# RamanPowerBoard.net
KiCad netlist of a schematic drawn in Altium Designer
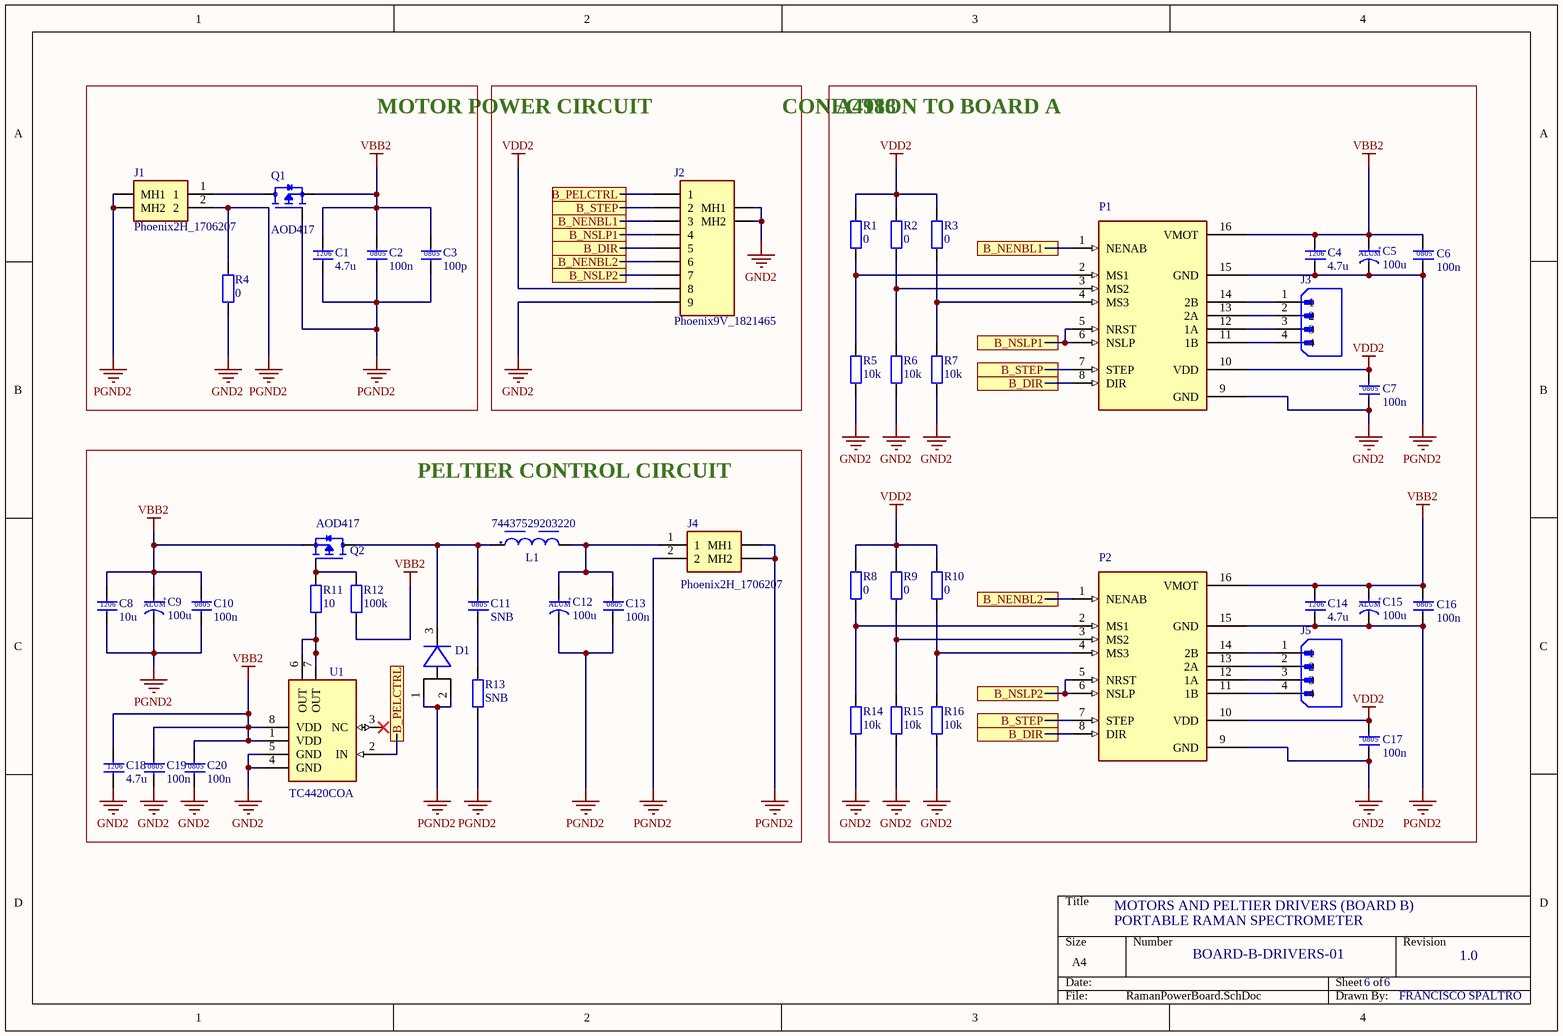
[diagram p0: RamanPowerBoard.SchDoc]

(export (version "E")
  (design (tool "Eeschema 10.0.6"))
  (components
    (comp (ref "C1")
      (value "4.7u")
      (footprint "CAP_1206")
      (description "Taiyo Yuden UMK316AB7475KL-T")
      (libsource (lib "Components") (part "CAP_1206"))
    )
    (comp (ref "C2")
      (value "100n")
      (footprint "RES_0805")
      (description "0805 Capacitor without polarity")
      (libsource (lib "Components") (part "CAP_0805"))
    )
    (comp (ref "C3")
      (value "100p")
      (footprint "RES_0805")
      (description "0805 Capacitor without polarity")
      (libsource (lib "Components") (part "CAP_0805"))
    )
    (comp (ref "C4")
      (value "4.7u")
      (footprint "CAP_1206")
      (description "Taiyo Yuden UMK316AB7475KL-T")
      (libsource (lib "Components") (part "CAP_1206"))
    )
    (comp (ref "C5")
      (value "100u")
      (footprint "CAP_EEFK_D8_PAN-M")
      (description "Panasonic EEE-FK1V101XP")
      (libsource (lib "Components") (part "CAP_RAD_POL"))
    )
    (comp (ref "C6")
      (value "100n")
      (footprint "RES_0805")
      (description "0805 Capacitor without polarity")
      (libsource (lib "Components") (part "CAP_0805"))
    )
    (comp (ref "C7")
      (value "100n")
      (footprint "RES_0805")
      (description "0805 Capacitor without polarity")
      (libsource (lib "Components") (part "CAP_0805"))
    )
    (comp (ref "C8")
      (value "10u")
      (footprint "CAP_1206")
      (description "Samsung CL31A106KAHNNNE")
      (libsource (lib "Components") (part "CAP_1206"))
    )
    (comp (ref "C9")
      (value "100u")
      (footprint "CAP_EEFK_D8_PAN-M")
      (description "Panasonic EEE-FK1V101XP")
      (libsource (lib "Components") (part "CAP_RAD_POL"))
    )
    (comp (ref "C10")
      (value "100n")
      (footprint "RES_0805")
      (description "0805 Capacitor without polarity")
      (libsource (lib "Components") (part "CAP_0805"))
    )
    (comp (ref "C11")
      (value "SNB")
      (footprint "RES_0805")
      (description "0805 Capacitor without polarity")
      (libsource (lib "Components") (part "CAP_0805"))
    )
    (comp (ref "C12")
      (value "100u")
      (footprint "CAP_EEFK_D8_PAN-M")
      (description "Panasonic EEE-FK1V101XP")
      (libsource (lib "Components") (part "CAP_RAD_POL"))
    )
    (comp (ref "C13")
      (value "100n")
      (footprint "RES_0805")
      (description "0805 Capacitor without polarity")
      (libsource (lib "Components") (part "CAP_0805"))
    )
    (comp (ref "C14")
      (value "4.7u")
      (footprint "CAP_1206")
      (description "Taiyo Yuden UMK316AB7475KL-T")
      (libsource (lib "Components") (part "CAP_1206"))
    )
    (comp (ref "C15")
      (value "100u")
      (footprint "CAP_EEFK_D8_PAN-M")
      (description "Panasonic EEE-FK1V101XP")
      (libsource (lib "Components") (part "CAP_RAD_POL"))
    )
    (comp (ref "C16")
      (value "100n")
      (footprint "RES_0805")
      (description "0805 Capacitor without polarity")
      (libsource (lib "Components") (part "CAP_0805"))
    )
    (comp (ref "C17")
      (value "100n")
      (footprint "RES_0805")
      (description "0805 Capacitor without polarity")
      (libsource (lib "Components") (part "CAP_0805"))
    )
    (comp (ref "C18")
      (value "4.7u")
      (footprint "CAP_1206")
      (description "Taiyo Yuden UMK316AB7475KL-T")
      (libsource (lib "Components") (part "CAP_1206"))
    )
    (comp (ref "C19")
      (value "100n")
      (footprint "RES_0805")
      (description "0805 Capacitor without polarity")
      (libsource (lib "Components") (part "CAP_0805"))
    )
    (comp (ref "C20")
      (value "100n")
      (footprint "RES_0805")
      (description "0805 Capacitor without polarity")
      (libsource (lib "Components") (part "CAP_0805"))
    )
    (comp (ref "D1")
      (value "DIODE_FSV15150V")
      (footprint "FSV15150V_TO-277")
      (libsource (lib "Components") (part "DIODE_FSV15150V"))
    )
    (comp (ref "J1")
      (value "Phoenix2H_1706207")
      (footprint "PHOENIX_1706207")
      (fields (field (name "MP") "1706207"))
      (libsource (lib "Components") (part "Phoenix2H_1706207"))
    )
    (comp (ref "J2")
      (value "Phoenix9V_1821465")
      (footprint "PHOENIX_1821465")
      (fields (field (name "MF") "{'manufacturer': u'Phoenix Contact'}") (field (name "MP") "1821465"))
      (libsource (lib "Components") (part "Phoenix9V_1821465"))
    )
    (comp (ref "J3")
      (value "Molex_4P")
      (footprint "MOLEX_436500402")
      (description "Connector Header Through Hole, Right Angle 4 position 0.118 (3.00mm) (Molex 436500402)")
      (fields (field (name "MF") "Molex") (field (name "MP") "436500402"))
      (libsource (lib "Components") (part "Molex_4P"))
    )
    (comp (ref "J4")
      (value "Phoenix2H_1706207")
      (footprint "PHOENIX_1706207")
      (fields (field (name "MP") "1706207"))
      (libsource (lib "") (part "Phoenix2H_1706207_1"))
    )
    (comp (ref "J5")
      (value "Molex_4P")
      (footprint "MOLEX_436500402")
      (description "Connector Header Through Hole, Right Angle 4 position 0.118 (3.00mm) (Molex 436500402)")
      (fields (field (name "MF") "Molex") (field (name "MP") "436500402"))
      (libsource (lib "Components") (part "Molex_4P"))
    )
    (comp (ref "L1")
      (value "74437529203220")
      (footprint "WE-HCF_2920_ROUND")
      (fields (field (name "MF") "{'manufacturer': u'~{W}xfcrth Elektronik'}"))
      (libsource (lib "Components") (part "22uH_74437529203220"))
    )
    (comp (ref "P1")
      (value "2x8_PINES")
      (footprint "PINES8x2-sep")
      (libsource (lib "Components") (part "2x8_PINES"))
    )
    (comp (ref "P2")
      (value "2x8_PINES")
      (footprint "PINES8x2-sep")
      (libsource (lib "Components") (part "2x8_PINES"))
    )
    (comp (ref "Q1")
      (value "AOD417")
      (footprint "Components:DPAK228P994X240_3N")
      (description "P-Channel 30V 25A _Ta_ 2.5W _Ta_, 50W _Tc_ Surface Mount TO-252, _D-Pak_")
      (fields (field (name "MF") "Alpha &"))
      (libsource (lib "Components") (part "AOD417"))
    )
    (comp (ref "Q2")
      (value "AOD417")
      (footprint "Components:DPAK228P994X240_3N")
      (description "P-Channel 30V 25A _Ta_ 2.5W _Ta_, 50W _Tc_ Surface Mount TO-252, _D-Pak_")
      (fields (field (name "MF") "Alpha &"))
      (libsource (lib "Components") (part "AOD417"))
    )
    (comp (ref "R1")
      (value "0")
      (footprint "RES_0805")
      (description "Generic Capacitor")
      (libsource (lib "Components") (part "RES_0805"))
    )
    (comp (ref "R2")
      (value "0")
      (footprint "RES_0805")
      (description "Generic Capacitor")
      (libsource (lib "Components") (part "RES_0805"))
    )
    (comp (ref "R3")
      (value "0")
      (footprint "RES_0805")
      (description "Generic Capacitor")
      (libsource (lib "Components") (part "RES_0805"))
    )
    (comp (ref "R4")
      (value "0")
      (footprint "RES_0805")
      (description "Generic Capacitor")
      (libsource (lib "Components") (part "RES_0805"))
    )
    (comp (ref "R5")
      (value "10k")
      (footprint "RES_0805")
      (description "Generic Capacitor")
      (libsource (lib "Components") (part "RES_0805"))
    )
    (comp (ref "R6")
      (value "10k")
      (footprint "RES_0805")
      (description "Generic Capacitor")
      (libsource (lib "Components") (part "RES_0805"))
    )
    (comp (ref "R7")
      (value "10k")
      (footprint "RES_0805")
      (description "Generic Capacitor")
      (libsource (lib "Components") (part "RES_0805"))
    )
    (comp (ref "R8")
      (value "0")
      (footprint "RES_0805")
      (description "Generic Capacitor")
      (libsource (lib "Components") (part "RES_0805"))
    )
    (comp (ref "R9")
      (value "0")
      (footprint "RES_0805")
      (description "Generic Capacitor")
      (libsource (lib "Components") (part "RES_0805"))
    )
    (comp (ref "R10")
      (value "0")
      (footprint "RES_0805")
      (description "Generic Capacitor")
      (libsource (lib "Components") (part "RES_0805"))
    )
    (comp (ref "R11")
      (value "10")
      (footprint "RES_0805")
      (description "Generic Capacitor")
      (libsource (lib "Components") (part "RES_0805"))
    )
    (comp (ref "R12")
      (value "100k")
      (footprint "RES_0805")
      (description "Generic Capacitor")
      (libsource (lib "Components") (part "RES_0805"))
    )
    (comp (ref "R13")
      (value "SNB")
      (footprint "RES_0805")
      (description "Generic Capacitor")
      (libsource (lib "Components") (part "RES_0805"))
    )
    (comp (ref "R14")
      (value "10k")
      (footprint "RES_0805")
      (description "Generic Capacitor")
      (libsource (lib "Components") (part "RES_0805"))
    )
    (comp (ref "R15")
      (value "10k")
      (footprint "RES_0805")
      (description "Generic Capacitor")
      (libsource (lib "Components") (part "RES_0805"))
    )
    (comp (ref "R16")
      (value "10k")
      (footprint "RES_0805")
      (description "Generic Capacitor")
      (libsource (lib "Components") (part "RES_0805"))
    )
    (comp (ref "U1")
      (value "TC4420COA")
      (footprint "SOIC127P599X175-8N")
      (fields (field (name "MF") "Microchip Technology"))
      (libsource (lib "Components") (part "TC4420COA"))
    )
  )
  (nets
    (net (code "1") (name "/B_DIR") (class "Default")
      (node (ref "J2") (pin "5") (pinfunction "5_5") (pintype "passive"))
      (node (ref "P1") (pin "8") (pinfunction "DIR_8") (pintype "input"))
      (node (ref "P2") (pin "8") (pinfunction "DIR_8") (pintype "input"))
    )
    (net (code "2") (name "/B_NENBL1") (class "Default")
      (node (ref "J2") (pin "3") (pinfunction "3_3") (pintype "passive"))
      (node (ref "P1") (pin "1") (pinfunction "NENAB_1") (pintype "input"))
    )
    (net (code "3") (name "/B_NENBL2") (class "Default")
      (node (ref "J2") (pin "6") (pinfunction "6_6") (pintype "passive"))
      (node (ref "P2") (pin "1") (pinfunction "NENAB_1") (pintype "input"))
    )
    (net (code "4") (name "/B_NSLP1") (class "Default")
      (node (ref "J2") (pin "4") (pinfunction "4_4") (pintype "passive"))
      (node (ref "P1") (pin "5") (pinfunction "NRST_5") (pintype "input"))
      (node (ref "P1") (pin "6") (pinfunction "NSLP_6") (pintype "input"))
    )
    (net (code "5") (name "/B_NSLP2") (class "Default")
      (node (ref "J2") (pin "7") (pinfunction "7_7") (pintype "passive"))
      (node (ref "P2") (pin "5") (pinfunction "NRST_5") (pintype "input"))
      (node (ref "P2") (pin "6") (pinfunction "NSLP_6") (pintype "input"))
    )
    (net (code "6") (name "/B_PELCTRL") (class "Default")
      (node (ref "J2") (pin "1") (pinfunction "1_1") (pintype "passive"))
      (node (ref "U1") (pin "2") (pinfunction "IN_2") (pintype "input"))
    )
    (net (code "7") (name "/B_STEP") (class "Default")
      (node (ref "J2") (pin "2") (pinfunction "2_2") (pintype "passive"))
      (node (ref "P1") (pin "7") (pinfunction "STEP_7") (pintype "input"))
      (node (ref "P2") (pin "7") (pinfunction "STEP_7") (pintype "input"))
    )
    (net (code "8") (name "GND2") (class "Default")
      (node (ref "C17") (pin "2") (pinfunction "2_2") (pintype "passive"))
      (node (ref "C18") (pin "2") (pinfunction "2_2") (pintype "passive"))
      (node (ref "C19") (pin "2") (pinfunction "2_2") (pintype "passive"))
      (node (ref "C20") (pin "2") (pinfunction "2_2") (pintype "passive"))
      (node (ref "C7") (pin "2") (pinfunction "2_2") (pintype "passive"))
      (node (ref "J2") (pin "9") (pinfunction "9_9") (pintype "power_in"))
      (node (ref "J2") (pin "MH1") (pinfunction "MH1_MH1") (pintype "passive"))
      (node (ref "J2") (pin "MH2") (pinfunction "MH2_MH2") (pintype "passive"))
      (node (ref "P1") (pin "9") (pinfunction "GND_9") (pintype "passive"))
      (node (ref "P2") (pin "9") (pinfunction "GND_9") (pintype "passive"))
      (node (ref "R14") (pin "1") (pinfunction "1_1") (pintype "passive"))
      (node (ref "R15") (pin "1") (pinfunction "1_1") (pintype "passive"))
      (node (ref "R16") (pin "1") (pinfunction "1_1") (pintype "passive"))
      (node (ref "R4") (pin "1") (pinfunction "1_1") (pintype "passive"))
      (node (ref "R5") (pin "1") (pinfunction "1_1") (pintype "passive"))
      (node (ref "R6") (pin "1") (pinfunction "1_1") (pintype "passive"))
      (node (ref "R7") (pin "1") (pinfunction "1_1") (pintype "passive"))
      (node (ref "U1") (pin "4") (pinfunction "GND_4") (pintype "power_in"))
      (node (ref "U1") (pin "5") (pinfunction "GND_5") (pintype "power_in"))
    )
    (net (code "9") (name "Net-(C11-Pad2)") (class "Default")
      (node (ref "C11") (pin "2") (pinfunction "2_2") (pintype "passive"))
      (node (ref "R13") (pin "2") (pinfunction "2_2") (pintype "passive"))
    )
    (net (code "10") (name "Net-(C12-Pad1)") (class "Default")
      (node (ref "C12") (pin "1") (pinfunction "1_1") (pintype "passive"))
      (node (ref "C13") (pin "1") (pinfunction "1_1") (pintype "passive"))
      (node (ref "J4") (pin "1") (pinfunction "1_1") (pintype "passive"))
      (node (ref "L1") (pin "2") (pinfunction "2_2") (pintype "passive"))
    )
    (net (code "11") (name "Net-(D1-C)") (class "Default")
      (node (ref "C11") (pin "1") (pinfunction "1_1") (pintype "passive"))
      (node (ref "D1") (pin "3") (pinfunction "C_3") (pintype "passive"))
      (node (ref "L1") (pin "1") (pinfunction "1_1") (pintype "passive"))
      (node (ref "Q2") (pin "4") (pinfunction "D_4") (pintype "passive"))
    )
    (net (code "12") (name "Net-(P1-1A)") (class "Default")
      (node (ref "J3") (pin "3") (pinfunction "3_3") (pintype "passive"))
      (node (ref "P1") (pin "12") (pinfunction "1A_12") (pintype "passive"))
    )
    (net (code "13") (name "Net-(P1-1B)") (class "Default")
      (node (ref "J3") (pin "4") (pinfunction "4_4") (pintype "passive"))
      (node (ref "P1") (pin "11") (pinfunction "1B_11") (pintype "passive"))
    )
    (net (code "14") (name "Net-(P1-2A)") (class "Default")
      (node (ref "J3") (pin "2") (pinfunction "2_2") (pintype "passive"))
      (node (ref "P1") (pin "13") (pinfunction "2A_13") (pintype "passive"))
    )
    (net (code "15") (name "Net-(P1-2B)") (class "Default")
      (node (ref "J3") (pin "1") (pinfunction "1_1") (pintype "passive"))
      (node (ref "P1") (pin "14") (pinfunction "2B_14") (pintype "passive"))
    )
    (net (code "16") (name "Net-(P1-MS1)") (class "Default")
      (node (ref "P1") (pin "2") (pinfunction "MS1_2") (pintype "input"))
      (node (ref "R1") (pin "1") (pinfunction "1_1") (pintype "passive"))
      (node (ref "R5") (pin "2") (pinfunction "2_2") (pintype "passive"))
    )
    (net (code "17") (name "Net-(P1-MS2)") (class "Default")
      (node (ref "P1") (pin "3") (pinfunction "MS2_3") (pintype "input"))
      (node (ref "R2") (pin "1") (pinfunction "1_1") (pintype "passive"))
      (node (ref "R6") (pin "2") (pinfunction "2_2") (pintype "passive"))
    )
    (net (code "18") (name "Net-(P1-MS3)") (class "Default")
      (node (ref "P1") (pin "4") (pinfunction "MS3_4") (pintype "input"))
      (node (ref "R3") (pin "1") (pinfunction "1_1") (pintype "passive"))
      (node (ref "R7") (pin "2") (pinfunction "2_2") (pintype "passive"))
    )
    (net (code "19") (name "Net-(P2-1A)") (class "Default")
      (node (ref "J5") (pin "3") (pinfunction "3_3") (pintype "passive"))
      (node (ref "P2") (pin "12") (pinfunction "1A_12") (pintype "passive"))
    )
    (net (code "20") (name "Net-(P2-1B)") (class "Default")
      (node (ref "J5") (pin "4") (pinfunction "4_4") (pintype "passive"))
      (node (ref "P2") (pin "11") (pinfunction "1B_11") (pintype "passive"))
    )
    (net (code "21") (name "Net-(P2-2A)") (class "Default")
      (node (ref "J5") (pin "2") (pinfunction "2_2") (pintype "passive"))
      (node (ref "P2") (pin "13") (pinfunction "2A_13") (pintype "passive"))
    )
    (net (code "22") (name "Net-(P2-2B)") (class "Default")
      (node (ref "J5") (pin "1") (pinfunction "1_1") (pintype "passive"))
      (node (ref "P2") (pin "14") (pinfunction "2B_14") (pintype "passive"))
    )
    (net (code "23") (name "Net-(P2-MS1)") (class "Default")
      (node (ref "P2") (pin "2") (pinfunction "MS1_2") (pintype "input"))
      (node (ref "R14") (pin "2") (pinfunction "2_2") (pintype "passive"))
      (node (ref "R8") (pin "1") (pinfunction "1_1") (pintype "passive"))
    )
    (net (code "24") (name "Net-(P2-MS2)") (class "Default")
      (node (ref "P2") (pin "3") (pinfunction "MS2_3") (pintype "input"))
      (node (ref "R15") (pin "2") (pinfunction "2_2") (pintype "passive"))
      (node (ref "R9") (pin "1") (pinfunction "1_1") (pintype "passive"))
    )
    (net (code "25") (name "Net-(P2-MS3)") (class "Default")
      (node (ref "P2") (pin "4") (pinfunction "MS3_4") (pintype "input"))
      (node (ref "R10") (pin "1") (pinfunction "1_1") (pintype "passive"))
      (node (ref "R16") (pin "2") (pinfunction "2_2") (pintype "passive"))
    )
    (net (code "26") (name "Net-(Q1-D)") (class "Default")
      (node (ref "J1") (pin "1") (pinfunction "1_1") (pintype "power_in"))
      (node (ref "Q1") (pin "4") (pinfunction "D_4") (pintype "passive"))
    )
    (net (code "27") (name "Net-(Q2-G)") (class "Default")
      (node (ref "Q2") (pin "1") (pinfunction "G_1") (pintype "passive"))
      (node (ref "R11") (pin "2") (pinfunction "2_2") (pintype "passive"))
      (node (ref "R12") (pin "2") (pinfunction "2_2") (pintype "passive"))
    )
    (net (code "28") (name "Net-(R11-Pad1)") (class "Default")
      (node (ref "R11") (pin "1") (pinfunction "1_1") (pintype "passive"))
      (node (ref "U1") (pin "6") (pinfunction "OUT_6") (pintype "passive"))
      (node (ref "U1") (pin "7") (pinfunction "OUT_7") (pintype "passive"))
    )
    (net (code "29") (name "PGND2") (class "Default")
      (node (ref "C1") (pin "2") (pinfunction "2_2") (pintype "passive"))
      (node (ref "C10") (pin "2") (pinfunction "2_2") (pintype "passive"))
      (node (ref "C12") (pin "2") (pinfunction "2_2") (pintype "passive"))
      (node (ref "C13") (pin "2") (pinfunction "2_2") (pintype "passive"))
      (node (ref "C14") (pin "2") (pinfunction "2_2") (pintype "passive"))
      (node (ref "C15") (pin "2") (pinfunction "2_2") (pintype "passive"))
      (node (ref "C16") (pin "2") (pinfunction "2_2") (pintype "passive"))
      (node (ref "C2") (pin "2") (pinfunction "2_2") (pintype "passive"))
      (node (ref "C3") (pin "2") (pinfunction "2_2") (pintype "passive"))
      (node (ref "C4") (pin "2") (pinfunction "2_2") (pintype "passive"))
      (node (ref "C5") (pin "2") (pinfunction "2_2") (pintype "passive"))
      (node (ref "C6") (pin "2") (pinfunction "2_2") (pintype "passive"))
      (node (ref "C8") (pin "2") (pinfunction "2_2") (pintype "passive"))
      (node (ref "C9") (pin "2") (pinfunction "2_2") (pintype "passive"))
      (node (ref "D1") (pin "1") (pinfunction "A_1") (pintype "passive"))
      (node (ref "D1") (pin "2") (pinfunction "2_2") (pintype "passive"))
      (node (ref "J1") (pin "2") (pinfunction "2_2") (pintype "power_in"))
      (node (ref "J1") (pin "MH1") (pinfunction "MH1_MH1") (pintype "passive"))
      (node (ref "J1") (pin "MH2") (pinfunction "MH2_MH2") (pintype "passive"))
      (node (ref "J4") (pin "2") (pinfunction "2_2") (pintype "passive"))
      (node (ref "J4") (pin "MH1") (pinfunction "MH1_MH1") (pintype "passive"))
      (node (ref "J4") (pin "MH2") (pinfunction "MH2_MH2") (pintype "passive"))
      (node (ref "P1") (pin "15") (pinfunction "GND_15") (pintype "passive"))
      (node (ref "P2") (pin "15") (pinfunction "GND_15") (pintype "passive"))
      (node (ref "Q1") (pin "1") (pinfunction "G_1") (pintype "passive"))
      (node (ref "R13") (pin "1") (pinfunction "1_1") (pintype "passive"))
      (node (ref "R4") (pin "2") (pinfunction "2_2") (pintype "passive"))
    )
    (net (code "30") (name "VBB2") (class "Default")
      (node (ref "C1") (pin "1") (pinfunction "1_1") (pintype "passive"))
      (node (ref "C10") (pin "1") (pinfunction "1_1") (pintype "passive"))
      (node (ref "C14") (pin "1") (pinfunction "1_1") (pintype "passive"))
      (node (ref "C15") (pin "1") (pinfunction "1_1") (pintype "passive"))
      (node (ref "C16") (pin "1") (pinfunction "1_1") (pintype "passive"))
      (node (ref "C18") (pin "1") (pinfunction "1_1") (pintype "passive"))
      (node (ref "C19") (pin "1") (pinfunction "1_1") (pintype "passive"))
      (node (ref "C2") (pin "1") (pinfunction "1_1") (pintype "passive"))
      (node (ref "C20") (pin "1") (pinfunction "1_1") (pintype "passive"))
      (node (ref "C3") (pin "1") (pinfunction "1_1") (pintype "passive"))
      (node (ref "C4") (pin "1") (pinfunction "1_1") (pintype "passive"))
      (node (ref "C5") (pin "1") (pinfunction "1_1") (pintype "passive"))
      (node (ref "C6") (pin "1") (pinfunction "1_1") (pintype "passive"))
      (node (ref "C8") (pin "1") (pinfunction "1_1") (pintype "passive"))
      (node (ref "C9") (pin "1") (pinfunction "1_1") (pintype "passive"))
      (node (ref "P1") (pin "16") (pinfunction "VMOT_16") (pintype "passive"))
      (node (ref "P2") (pin "16") (pinfunction "VMOT_16") (pintype "passive"))
      (node (ref "Q1") (pin "3") (pinfunction "S_3") (pintype "passive"))
      (node (ref "Q2") (pin "3") (pinfunction "S_3") (pintype "passive"))
      (node (ref "R12") (pin "1") (pinfunction "1_1") (pintype "passive"))
      (node (ref "U1") (pin "1") (pinfunction "VDD_1") (pintype "power_in"))
      (node (ref "U1") (pin "8") (pinfunction "VDD_8") (pintype "power_in"))
    )
    (net (code "31") (name "VDD2") (class "Default")
      (node (ref "C17") (pin "1") (pinfunction "1_1") (pintype "passive"))
      (node (ref "C7") (pin "1") (pinfunction "1_1") (pintype "passive"))
      (node (ref "J2") (pin "8") (pinfunction "8_8") (pintype "power_in"))
      (node (ref "P1") (pin "10") (pinfunction "VDD_10") (pintype "passive"))
      (node (ref "P2") (pin "10") (pinfunction "VDD_10") (pintype "passive"))
      (node (ref "R1") (pin "2") (pinfunction "2_2") (pintype "passive"))
      (node (ref "R10") (pin "2") (pinfunction "2_2") (pintype "passive"))
      (node (ref "R2") (pin "2") (pinfunction "2_2") (pintype "passive"))
      (node (ref "R3") (pin "2") (pinfunction "2_2") (pintype "passive"))
      (node (ref "R8") (pin "2") (pinfunction "2_2") (pintype "passive"))
      (node (ref "R9") (pin "2") (pinfunction "2_2") (pintype "passive"))
    )
    (net (code "32") (name "unconnected-(U1-NC-Pad3)") (class "Default")
      (node (ref "U1") (pin "3") (pinfunction "NC_3") (pintype "bidirectional+no_connect"))
    )
  )
)
